# VacPack_RevA.net
KiCad netlist of a schematic drawn in EAGLE
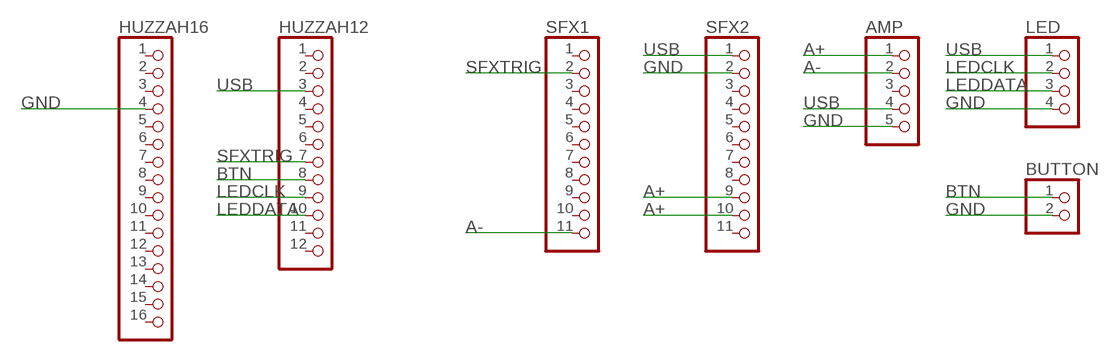
[diagram p0: schematic, sheet 1]

(export (version "E")
  (design (tool "Eeschema 10.0.6"))
  (components
    (comp (ref "AMP")
      (value "PINHD-1X5")
      (footprint "eagle-import:1X05")
      (libsource (lib "eagle-import") (part "PINHD-1X5"))
    )
    (comp (ref "BUTTON")
      (value "PINHD-1X2")
      (footprint "eagle-import:1X02")
      (libsource (lib "eagle-import") (part "PINHD-1X2"))
    )
    (comp (ref "HUZZAH12")
      (value "PINHD-1X12")
      (footprint "eagle-import:1X12")
      (libsource (lib "eagle-import") (part "PINHD-1X12"))
    )
    (comp (ref "HUZZAH16")
      (value "PINHD-1X16")
      (footprint "eagle-import:1X16")
      (libsource (lib "eagle-import") (part "PINHD-1X16"))
    )
    (comp (ref "LED")
      (value "PINHD-1X4")
      (footprint "eagle-import:1X04")
      (libsource (lib "eagle-import") (part "PINHD-1X4"))
    )
    (comp (ref "SFX1")
      (value "PINHD-1X11")
      (footprint "eagle-import:1X11")
      (libsource (lib "eagle-import") (part "PINHD-1X11"))
    )
    (comp (ref "SFX2")
      (value "PINHD-1X11")
      (footprint "eagle-import:1X11")
      (libsource (lib "eagle-import") (part "PINHD-1X11"))
    )
  )
  (nets
    (net (code "1") (name "/A+") (class "Default")
      (node (ref "AMP") (pin "1") (pinfunction "1_1") (pintype "passive"))
      (node (ref "SFX2") (pin "10") (pinfunction "10_10") (pintype "passive"))
      (node (ref "SFX2") (pin "9") (pinfunction "9_9") (pintype "passive"))
    )
    (net (code "2") (name "/A-") (class "Default")
      (node (ref "AMP") (pin "2") (pinfunction "2_2") (pintype "passive"))
      (node (ref "SFX1") (pin "11") (pinfunction "11_11") (pintype "passive"))
    )
    (net (code "3") (name "/BTN") (class "Default")
      (node (ref "BUTTON") (pin "1") (pinfunction "1_1") (pintype "passive"))
      (node (ref "HUZZAH12") (pin "8") (pinfunction "8_8") (pintype "passive"))
    )
    (net (code "4") (name "/GND") (class "Default")
      (node (ref "AMP") (pin "5") (pinfunction "5_5") (pintype "passive"))
      (node (ref "BUTTON") (pin "2") (pinfunction "2_2") (pintype "passive"))
      (node (ref "HUZZAH16") (pin "4") (pinfunction "4_4") (pintype "passive"))
      (node (ref "LED") (pin "4") (pinfunction "4_4") (pintype "passive"))
      (node (ref "SFX2") (pin "2") (pinfunction "2_2") (pintype "passive"))
    )
    (net (code "5") (name "/LEDCLK") (class "Default")
      (node (ref "HUZZAH12") (pin "9") (pinfunction "9_9") (pintype "passive"))
      (node (ref "LED") (pin "2") (pinfunction "2_2") (pintype "passive"))
    )
    (net (code "6") (name "/LEDDATA") (class "Default")
      (node (ref "HUZZAH12") (pin "10") (pinfunction "10_10") (pintype "passive"))
      (node (ref "LED") (pin "3") (pinfunction "3_3") (pintype "passive"))
    )
    (net (code "7") (name "/SFXTRIG") (class "Default")
      (node (ref "HUZZAH12") (pin "7") (pinfunction "7_7") (pintype "passive"))
      (node (ref "SFX1") (pin "2") (pinfunction "2_2") (pintype "passive"))
    )
    (net (code "8") (name "/USB") (class "Default")
      (node (ref "AMP") (pin "4") (pinfunction "4_4") (pintype "passive"))
      (node (ref "HUZZAH12") (pin "3") (pinfunction "3_3") (pintype "passive"))
      (node (ref "LED") (pin "1") (pinfunction "1_1") (pintype "passive"))
      (node (ref "SFX2") (pin "1") (pinfunction "1_1") (pintype "passive"))
    )
    (net (code "9") (name "unconnected-(AMP-Pad3)") (class "Default")
      (node (ref "AMP") (pin "3") (pinfunction "3_3") (pintype "passive"))
    )
    (net (code "10") (name "unconnected-(HUZZAH12-Pad1)") (class "Default")
      (node (ref "HUZZAH12") (pin "1") (pinfunction "1_1") (pintype "passive"))
    )
    (net (code "11") (name "unconnected-(HUZZAH12-Pad2)") (class "Default")
      (node (ref "HUZZAH12") (pin "2") (pinfunction "2_2") (pintype "passive"))
    )
    (net (code "12") (name "unconnected-(HUZZAH12-Pad4)") (class "Default")
      (node (ref "HUZZAH12") (pin "4") (pinfunction "4_4") (pintype "passive"))
    )
    (net (code "13") (name "unconnected-(HUZZAH12-Pad5)") (class "Default")
      (node (ref "HUZZAH12") (pin "5") (pinfunction "5_5") (pintype "passive"))
    )
    (net (code "14") (name "unconnected-(HUZZAH12-Pad6)") (class "Default")
      (node (ref "HUZZAH12") (pin "6") (pinfunction "6_6") (pintype "passive"))
    )
    (net (code "15") (name "unconnected-(HUZZAH12-Pad11)") (class "Default")
      (node (ref "HUZZAH12") (pin "11") (pinfunction "11_11") (pintype "passive"))
    )
    (net (code "16") (name "unconnected-(HUZZAH12-Pad12)") (class "Default")
      (node (ref "HUZZAH12") (pin "12") (pinfunction "12_12") (pintype "passive"))
    )
    (net (code "17") (name "unconnected-(HUZZAH16-Pad1)") (class "Default")
      (node (ref "HUZZAH16") (pin "1") (pinfunction "1_1") (pintype "passive"))
    )
    (net (code "18") (name "unconnected-(HUZZAH16-Pad2)") (class "Default")
      (node (ref "HUZZAH16") (pin "2") (pinfunction "2_2") (pintype "passive"))
    )
    (net (code "19") (name "unconnected-(HUZZAH16-Pad3)") (class "Default")
      (node (ref "HUZZAH16") (pin "3") (pinfunction "3_3") (pintype "passive"))
    )
    (net (code "20") (name "unconnected-(HUZZAH16-Pad5)") (class "Default")
      (node (ref "HUZZAH16") (pin "5") (pinfunction "5_5") (pintype "passive"))
    )
    (net (code "21") (name "unconnected-(HUZZAH16-Pad6)") (class "Default")
      (node (ref "HUZZAH16") (pin "6") (pinfunction "6_6") (pintype "passive"))
    )
    (net (code "22") (name "unconnected-(HUZZAH16-Pad7)") (class "Default")
      (node (ref "HUZZAH16") (pin "7") (pinfunction "7_7") (pintype "passive"))
    )
    (net (code "23") (name "unconnected-(HUZZAH16-Pad8)") (class "Default")
      (node (ref "HUZZAH16") (pin "8") (pinfunction "8_8") (pintype "passive"))
    )
    (net (code "24") (name "unconnected-(HUZZAH16-Pad9)") (class "Default")
      (node (ref "HUZZAH16") (pin "9") (pinfunction "9_9") (pintype "passive"))
    )
    (net (code "25") (name "unconnected-(HUZZAH16-Pad10)") (class "Default")
      (node (ref "HUZZAH16") (pin "10") (pinfunction "10_10") (pintype "passive"))
    )
    (net (code "26") (name "unconnected-(HUZZAH16-Pad11)") (class "Default")
      (node (ref "HUZZAH16") (pin "11") (pinfunction "11_11") (pintype "passive"))
    )
    (net (code "27") (name "unconnected-(HUZZAH16-Pad12)") (class "Default")
      (node (ref "HUZZAH16") (pin "12") (pinfunction "12_12") (pintype "passive"))
    )
    (net (code "28") (name "unconnected-(HUZZAH16-Pad13)") (class "Default")
      (node (ref "HUZZAH16") (pin "13") (pinfunction "13_13") (pintype "passive"))
    )
    (net (code "29") (name "unconnected-(HUZZAH16-Pad14)") (class "Default")
      (node (ref "HUZZAH16") (pin "14") (pinfunction "14_14") (pintype "passive"))
    )
    (net (code "30") (name "unconnected-(HUZZAH16-Pad15)") (class "Default")
      (node (ref "HUZZAH16") (pin "15") (pinfunction "15_15") (pintype "passive"))
    )
    (net (code "31") (name "unconnected-(HUZZAH16-Pad16)") (class "Default")
      (node (ref "HUZZAH16") (pin "16") (pinfunction "16_16") (pintype "passive"))
    )
    (net (code "32") (name "unconnected-(SFX1-Pad1)") (class "Default")
      (node (ref "SFX1") (pin "1") (pinfunction "1_1") (pintype "passive"))
    )
    (net (code "33") (name "unconnected-(SFX1-Pad3)") (class "Default")
      (node (ref "SFX1") (pin "3") (pinfunction "3_3") (pintype "passive"))
    )
    (net (code "34") (name "unconnected-(SFX1-Pad4)") (class "Default")
      (node (ref "SFX1") (pin "4") (pinfunction "4_4") (pintype "passive"))
    )
    (net (code "35") (name "unconnected-(SFX1-Pad5)") (class "Default")
      (node (ref "SFX1") (pin "5") (pinfunction "5_5") (pintype "passive"))
    )
    (net (code "36") (name "unconnected-(SFX1-Pad6)") (class "Default")
      (node (ref "SFX1") (pin "6") (pinfunction "6_6") (pintype "passive"))
    )
    (net (code "37") (name "unconnected-(SFX1-Pad7)") (class "Default")
      (node (ref "SFX1") (pin "7") (pinfunction "7_7") (pintype "passive"))
    )
    (net (code "38") (name "unconnected-(SFX1-Pad8)") (class "Default")
      (node (ref "SFX1") (pin "8") (pinfunction "8_8") (pintype "passive"))
    )
    (net (code "39") (name "unconnected-(SFX1-Pad9)") (class "Default")
      (node (ref "SFX1") (pin "9") (pinfunction "9_9") (pintype "passive"))
    )
    (net (code "40") (name "unconnected-(SFX1-Pad10)") (class "Default")
      (node (ref "SFX1") (pin "10") (pinfunction "10_10") (pintype "passive"))
    )
    (net (code "41") (name "unconnected-(SFX2-Pad3)") (class "Default")
      (node (ref "SFX2") (pin "3") (pinfunction "3_3") (pintype "passive"))
    )
    (net (code "42") (name "unconnected-(SFX2-Pad4)") (class "Default")
      (node (ref "SFX2") (pin "4") (pinfunction "4_4") (pintype "passive"))
    )
    (net (code "43") (name "unconnected-(SFX2-Pad5)") (class "Default")
      (node (ref "SFX2") (pin "5") (pinfunction "5_5") (pintype "passive"))
    )
    (net (code "44") (name "unconnected-(SFX2-Pad6)") (class "Default")
      (node (ref "SFX2") (pin "6") (pinfunction "6_6") (pintype "passive"))
    )
    (net (code "45") (name "unconnected-(SFX2-Pad7)") (class "Default")
      (node (ref "SFX2") (pin "7") (pinfunction "7_7") (pintype "passive"))
    )
    (net (code "46") (name "unconnected-(SFX2-Pad8)") (class "Default")
      (node (ref "SFX2") (pin "8") (pinfunction "8_8") (pintype "passive"))
    )
    (net (code "47") (name "unconnected-(SFX2-Pad11)") (class "Default")
      (node (ref "SFX2") (pin "11") (pinfunction "11_11") (pintype "passive"))
    )
  )
)
